# main.net
KiCad netlist of a schematic drawn in EAGLE
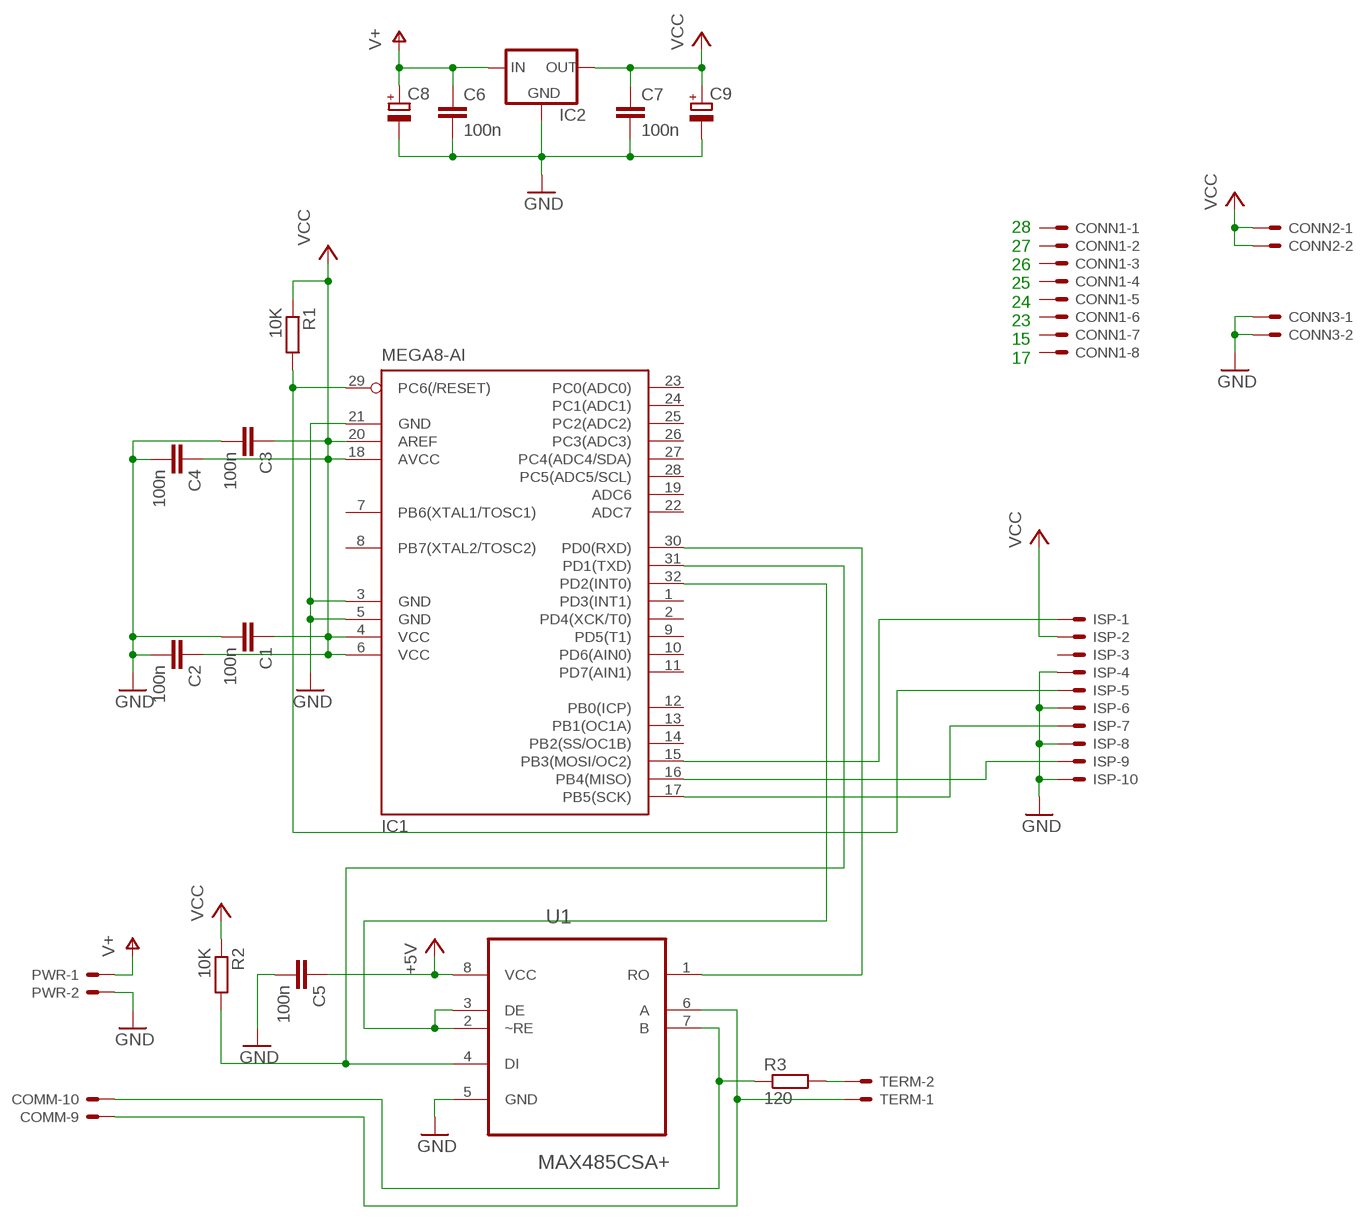
[diagram p0: schematic, sheet 1]

(export (version "E")
  (design (tool "Eeschema 10.0.6"))
  (components
    (comp (ref "C1")
      (value "100n")
      (footprint "eagle-import:C2.5-3")
      (libsource (lib "eagle-import") (part "C2,5-3"))
    )
    (comp (ref "C2")
      (value "100n")
      (footprint "eagle-import:C2.5-3")
      (libsource (lib "eagle-import") (part "C2,5-3"))
    )
    (comp (ref "C3")
      (value "100n")
      (footprint "eagle-import:C2.5-3")
      (libsource (lib "eagle-import") (part "C2,5-3"))
    )
    (comp (ref "C4")
      (value "100n")
      (footprint "eagle-import:C2.5-3")
      (libsource (lib "eagle-import") (part "C2,5-3"))
    )
    (comp (ref "C5")
      (value "100n")
      (footprint "eagle-import:C2.5-3")
      (libsource (lib "eagle-import") (part "C2,5-3"))
    )
    (comp (ref "C6")
      (value "100n")
      (footprint "eagle-import:C2.5-3")
      (libsource (lib "eagle-import") (part "C2,5-3"))
    )
    (comp (ref "C7")
      (value "100n")
      (footprint "eagle-import:C2.5-3")
      (libsource (lib "eagle-import") (part "C2,5-3"))
    )
    (comp (ref "C8")
      (value "CPOL-EU085CS-1AR")
      (footprint "eagle-import:085CS_1AR")
      (libsource (lib "eagle-import") (part "CPOL-EU085CS-1AR"))
    )
    (comp (ref "C9")
      (value "CPOL-EU085CS-1AR")
      (footprint "eagle-import:085CS_1AR")
      (libsource (lib "eagle-import") (part "CPOL-EU085CS-1AR"))
    )
    (comp (ref "COMM")
      (value "5566-10")
      (footprint "eagle-import:5566-10")
      (libsource (lib "eagle-import") (part "5566-10"))
    )
    (comp (ref "CONN1")
      (value "5566-10")
      (footprint "eagle-import:5566-10")
      (libsource (lib "eagle-import") (part "5566-10"))
    )
    (comp (ref "CONN2")
      (value "5566-10")
      (footprint "eagle-import:5566-10")
      (libsource (lib "eagle-import") (part "5566-10"))
    )
    (comp (ref "CONN3")
      (value "5566-10")
      (footprint "eagle-import:5566-10")
      (libsource (lib "eagle-import") (part "5566-10"))
    )
    (comp (ref "IC1")
      (value "MEGA8-AI")
      (footprint "eagle-import:TQFP32-08")
      (fields (field (name "MPN") "ATMEGA8-16AU"))
      (libsource (lib "eagle-import") (part "MEGA8-AI"))
    )
    (comp (ref "IC2")
      (value "78LXX")
      (footprint "eagle-import:78LXX")
      (libsource (lib "eagle-import") (part "78LXX"))
    )
    (comp (ref "ISP")
      (value "5566-10")
      (footprint "eagle-import:5566-10")
      (libsource (lib "eagle-import") (part "5566-10"))
    )
    (comp (ref "PWR")
      (value "5566-10")
      (footprint "eagle-import:5566-10")
      (libsource (lib "eagle-import") (part "5566-10"))
    )
    (comp (ref "R1")
      (value "10K")
      (footprint "eagle-import:M1206")
      (libsource (lib "eagle-import") (part "R-EU_M1206"))
    )
    (comp (ref "R2")
      (value "10K")
      (footprint "eagle-import:M1206")
      (libsource (lib "eagle-import") (part "R-EU_M1206"))
    )
    (comp (ref "R3")
      (value "120")
      (footprint "eagle-import:M1206")
      (libsource (lib "eagle-import") (part "R-EU_M1206"))
    )
    (comp (ref "TERM")
      (value "5566-10")
      (footprint "eagle-import:5566-10")
      (libsource (lib "eagle-import") (part "5566-10"))
    )
    (comp (ref "U1")
      (value "MAX485CSA+")
      (footprint "eagle-import:SOIC127P600X175-8N")
      (libsource (lib "eagle-import") (part "MAX485CSA+"))
    )
  )
  (nets
    (net (code "1") (name "+5V") (class "Default")
      (node (ref "C5") (pin "1") (pinfunction "1_1") (pintype "passive"))
      (node (ref "U1") (pin "8") (pinfunction "VCC_8") (pintype "power_in"))
    )
    (net (code "2") (name "GND") (class "Default")
      (node (ref "C1") (pin "2") (pinfunction "2_2") (pintype "passive"))
      (node (ref "C2") (pin "2") (pinfunction "2_2") (pintype "passive"))
      (node (ref "C3") (pin "2") (pinfunction "2_2") (pintype "passive"))
      (node (ref "C4") (pin "2") (pinfunction "2_2") (pintype "passive"))
      (node (ref "C5") (pin "2") (pinfunction "2_2") (pintype "passive"))
      (node (ref "C6") (pin "2") (pinfunction "2_2") (pintype "passive"))
      (node (ref "C7") (pin "2") (pinfunction "2_2") (pintype "passive"))
      (node (ref "C8") (pin "-") (pinfunction "-_-") (pintype "passive"))
      (node (ref "C9") (pin "-") (pinfunction "-_-") (pintype "passive"))
      (node (ref "CONN3") (pin "1") (pinfunction "S_1") (pintype "passive"))
      (node (ref "CONN3") (pin "2") (pinfunction "S_2") (pintype "passive"))
      (node (ref "IC1") (pin "21") (pinfunction "GND_21") (pintype "power_in"))
      (node (ref "IC1") (pin "3") (pinfunction "GND_3") (pintype "power_in"))
      (node (ref "IC1") (pin "5") (pinfunction "GND_5") (pintype "power_in"))
      (node (ref "IC2") (pin "GND") (pinfunction "GND_GND") (pintype "input"))
      (node (ref "ISP") (pin "10") (pinfunction "S_10") (pintype "passive"))
      (node (ref "ISP") (pin "4") (pinfunction "S_4") (pintype "passive"))
      (node (ref "ISP") (pin "6") (pinfunction "S_6") (pintype "passive"))
      (node (ref "ISP") (pin "8") (pinfunction "S_8") (pintype "passive"))
      (node (ref "PWR") (pin "2") (pinfunction "S_2") (pintype "passive"))
      (node (ref "U1") (pin "5") (pinfunction "GND_5") (pintype "passive"))
    )
    (net (code "3") (name "Net-(COMMB-S)") (class "Default")
      (node (ref "COMM") (pin "10") (pinfunction "S_10") (pintype "passive"))
      (node (ref "R3") (pin "1") (pinfunction "1_1") (pintype "passive"))
      (node (ref "U1") (pin "7") (pinfunction "B_7") (pintype "bidirectional"))
    )
    (net (code "4") (name "Net-(COMMJ-S)") (class "Default")
      (node (ref "COMM") (pin "9") (pinfunction "S_9") (pintype "passive"))
      (node (ref "TERM") (pin "1") (pinfunction "S_1") (pintype "passive"))
      (node (ref "U1") (pin "6") (pinfunction "A_6") (pintype "bidirectional"))
    )
    (net (code "5") (name "Net-(IC1-PB3(MOSI{slash}OC2))") (class "Default")
      (node (ref "IC1") (pin "15") (pinfunction "PB3(MOSI/OC2)_15") (pintype "bidirectional"))
      (node (ref "ISP") (pin "1") (pinfunction "S_1") (pintype "passive"))
    )
    (net (code "6") (name "Net-(IC1-PB4(MISO))") (class "Default")
      (node (ref "IC1") (pin "16") (pinfunction "PB4(MISO)_16") (pintype "bidirectional"))
      (node (ref "ISP") (pin "9") (pinfunction "S_9") (pintype "passive"))
    )
    (net (code "7") (name "Net-(IC1-PB5(SCK))") (class "Default")
      (node (ref "IC1") (pin "17") (pinfunction "PB5(SCK)_17") (pintype "bidirectional"))
      (node (ref "ISP") (pin "7") (pinfunction "S_7") (pintype "passive"))
    )
    (net (code "8") (name "Net-(IC1-PC6({slash}RESET))") (class "Default")
      (node (ref "IC1") (pin "29") (pinfunction "PC6(/RESET)_29") (pintype "bidirectional"))
      (node (ref "ISP") (pin "5") (pinfunction "S_5") (pintype "passive"))
      (node (ref "R1") (pin "2") (pinfunction "2_2") (pintype "passive"))
    )
    (net (code "9") (name "Net-(IC1-PD0(RXD))") (class "Default")
      (node (ref "IC1") (pin "30") (pinfunction "PD0(RXD)_30") (pintype "bidirectional"))
      (node (ref "U1") (pin "1") (pinfunction "RO_1") (pintype "output"))
    )
    (net (code "10") (name "Net-(IC1-PD1(TXD))") (class "Default")
      (node (ref "IC1") (pin "31") (pinfunction "PD1(TXD)_31") (pintype "bidirectional"))
      (node (ref "R2") (pin "2") (pinfunction "2_2") (pintype "passive"))
      (node (ref "U1") (pin "4") (pinfunction "DI_4") (pintype "input"))
    )
    (net (code "11") (name "Net-(IC1-PD2(INT0))") (class "Default")
      (node (ref "IC1") (pin "32") (pinfunction "PD2(INT0)_32") (pintype "bidirectional"))
      (node (ref "U1") (pin "2") (pinfunction "~{RE}_2") (pintype "input"))
      (node (ref "U1") (pin "3") (pinfunction "DE_3") (pintype "input"))
    )
    (net (code "12") (name "Net-(TERMC-S)") (class "Default")
      (node (ref "R3") (pin "2") (pinfunction "2_2") (pintype "passive"))
      (node (ref "TERM") (pin "2") (pinfunction "S_2") (pintype "passive"))
    )
    (net (code "13") (name "V+") (class "Default")
      (node (ref "C6") (pin "1") (pinfunction "1_1") (pintype "passive"))
      (node (ref "C8") (pin "+") (pinfunction "+_+") (pintype "passive"))
      (node (ref "IC2") (pin "IN") (pinfunction "IN_IN") (pintype "input"))
      (node (ref "PWR") (pin "1") (pinfunction "S_1") (pintype "passive"))
    )
    (net (code "14") (name "VCC") (class "Default")
      (node (ref "C1") (pin "1") (pinfunction "1_1") (pintype "passive"))
      (node (ref "C2") (pin "1") (pinfunction "1_1") (pintype "passive"))
      (node (ref "C3") (pin "1") (pinfunction "1_1") (pintype "passive"))
      (node (ref "C4") (pin "1") (pinfunction "1_1") (pintype "passive"))
      (node (ref "C7") (pin "1") (pinfunction "1_1") (pintype "passive"))
      (node (ref "C9") (pin "+") (pinfunction "+_+") (pintype "passive"))
      (node (ref "CONN2") (pin "1") (pinfunction "S_1") (pintype "passive"))
      (node (ref "CONN2") (pin "2") (pinfunction "S_2") (pintype "passive"))
      (node (ref "IC1") (pin "18") (pinfunction "AVCC_18") (pintype "power_in"))
      (node (ref "IC1") (pin "20") (pinfunction "AREF_20") (pintype "passive"))
      (node (ref "IC1") (pin "4") (pinfunction "VCC_4") (pintype "power_in"))
      (node (ref "IC1") (pin "6") (pinfunction "VCC_6") (pintype "power_in"))
      (node (ref "IC2") (pin "OUT") (pinfunction "OUT_OUT") (pintype "passive"))
      (node (ref "ISP") (pin "2") (pinfunction "S_2") (pintype "passive"))
      (node (ref "R1") (pin "1") (pinfunction "1_1") (pintype "passive"))
      (node (ref "R2") (pin "1") (pinfunction "1_1") (pintype "passive"))
    )
    (net (code "15") (name "unconnected-(CONN1A-S-Pad1)") (class "Default")
      (node (ref "CONN1") (pin "1") (pinfunction "S_1") (pintype "passive"))
    )
    (net (code "16") (name "unconnected-(CONN1C-S-Pad2)") (class "Default")
      (node (ref "CONN1") (pin "2") (pinfunction "S_2") (pintype "passive"))
    )
    (net (code "17") (name "unconnected-(CONN1D-S-Pad3)") (class "Default")
      (node (ref "CONN1") (pin "3") (pinfunction "S_3") (pintype "passive"))
    )
    (net (code "18") (name "unconnected-(CONN1E-S-Pad4)") (class "Default")
      (node (ref "CONN1") (pin "4") (pinfunction "S_4") (pintype "passive"))
    )
    (net (code "19") (name "unconnected-(CONN1F-S-Pad5)") (class "Default")
      (node (ref "CONN1") (pin "5") (pinfunction "S_5") (pintype "passive"))
    )
    (net (code "20") (name "unconnected-(CONN1G-S-Pad6)") (class "Default")
      (node (ref "CONN1") (pin "6") (pinfunction "S_6") (pintype "passive"))
    )
    (net (code "21") (name "unconnected-(CONN1H-S-Pad7)") (class "Default")
      (node (ref "CONN1") (pin "7") (pinfunction "S_7") (pintype "passive"))
    )
    (net (code "22") (name "unconnected-(CONN1I-S-Pad8)") (class "Default")
      (node (ref "CONN1") (pin "8") (pinfunction "S_8") (pintype "passive"))
    )
    (net (code "23") (name "unconnected-(IC1-ADC6-Pad19)") (class "Default")
      (node (ref "IC1") (pin "19") (pinfunction "ADC6_19") (pintype "bidirectional"))
    )
    (net (code "24") (name "unconnected-(IC1-ADC7-Pad22)") (class "Default")
      (node (ref "IC1") (pin "22") (pinfunction "ADC7_22") (pintype "bidirectional"))
    )
    (net (code "25") (name "unconnected-(IC1-PB0(ICP)-Pad12)") (class "Default")
      (node (ref "IC1") (pin "12") (pinfunction "PB0(ICP)_12") (pintype "bidirectional"))
    )
    (net (code "26") (name "unconnected-(IC1-PB1(OC1A)-Pad13)") (class "Default")
      (node (ref "IC1") (pin "13") (pinfunction "PB1(OC1A)_13") (pintype "bidirectional"))
    )
    (net (code "27") (name "unconnected-(IC1-PB2(SS{slash}OC1B)-Pad14)") (class "Default")
      (node (ref "IC1") (pin "14") (pinfunction "PB2(SS/OC1B)_14") (pintype "bidirectional"))
    )
    (net (code "28") (name "unconnected-(IC1-PB6(XTAL1{slash}TOSC1)-Pad7)") (class "Default")
      (node (ref "IC1") (pin "7") (pinfunction "PB6(XTAL1/TOSC1)_7") (pintype "bidirectional"))
    )
    (net (code "29") (name "unconnected-(IC1-PB7(XTAL2{slash}TOSC2)-Pad8)") (class "Default")
      (node (ref "IC1") (pin "8") (pinfunction "PB7(XTAL2/TOSC2)_8") (pintype "bidirectional"))
    )
    (net (code "30") (name "unconnected-(IC1-PC0(ADC0)-Pad23)") (class "Default")
      (node (ref "IC1") (pin "23") (pinfunction "PC0(ADC0)_23") (pintype "bidirectional"))
    )
    (net (code "31") (name "unconnected-(IC1-PC1(ADC1)-Pad24)") (class "Default")
      (node (ref "IC1") (pin "24") (pinfunction "PC1(ADC1)_24") (pintype "bidirectional"))
    )
    (net (code "32") (name "unconnected-(IC1-PC2(ADC2)-Pad25)") (class "Default")
      (node (ref "IC1") (pin "25") (pinfunction "PC2(ADC2)_25") (pintype "bidirectional"))
    )
    (net (code "33") (name "unconnected-(IC1-PC3(ADC3)-Pad26)") (class "Default")
      (node (ref "IC1") (pin "26") (pinfunction "PC3(ADC3)_26") (pintype "bidirectional"))
    )
    (net (code "34") (name "unconnected-(IC1-PC4(ADC4{slash}SDA)-Pad27)") (class "Default")
      (node (ref "IC1") (pin "27") (pinfunction "PC4(ADC4/SDA)_27") (pintype "bidirectional"))
    )
    (net (code "35") (name "unconnected-(IC1-PC5(ADC5{slash}SCL)-Pad28)") (class "Default")
      (node (ref "IC1") (pin "28") (pinfunction "PC5(ADC5/SCL)_28") (pintype "bidirectional"))
    )
    (net (code "36") (name "unconnected-(IC1-PD3(INT1)-Pad1)") (class "Default")
      (node (ref "IC1") (pin "1") (pinfunction "PD3(INT1)_1") (pintype "bidirectional"))
    )
    (net (code "37") (name "unconnected-(IC1-PD4(XCK{slash}T0)-Pad2)") (class "Default")
      (node (ref "IC1") (pin "2") (pinfunction "PD4(XCK/T0)_2") (pintype "bidirectional"))
    )
    (net (code "38") (name "unconnected-(IC1-PD5(T1)-Pad9)") (class "Default")
      (node (ref "IC1") (pin "9") (pinfunction "PD5(T1)_9") (pintype "bidirectional"))
    )
    (net (code "39") (name "unconnected-(IC1-PD6(AIN0)-Pad10)") (class "Default")
      (node (ref "IC1") (pin "10") (pinfunction "PD6(AIN0)_10") (pintype "bidirectional"))
    )
    (net (code "40") (name "unconnected-(IC1-PD7(AIN1)-Pad11)") (class "Default")
      (node (ref "IC1") (pin "11") (pinfunction "PD7(AIN1)_11") (pintype "bidirectional"))
    )
    (net (code "41") (name "unconnected-(ISPD-S-Pad3)") (class "Default")
      (node (ref "ISP") (pin "3") (pinfunction "S_3") (pintype "passive"))
    )
  )
)
